# ArduinoUnoShield.net
KiCad netlist of a schematic drawn in Altium Designer
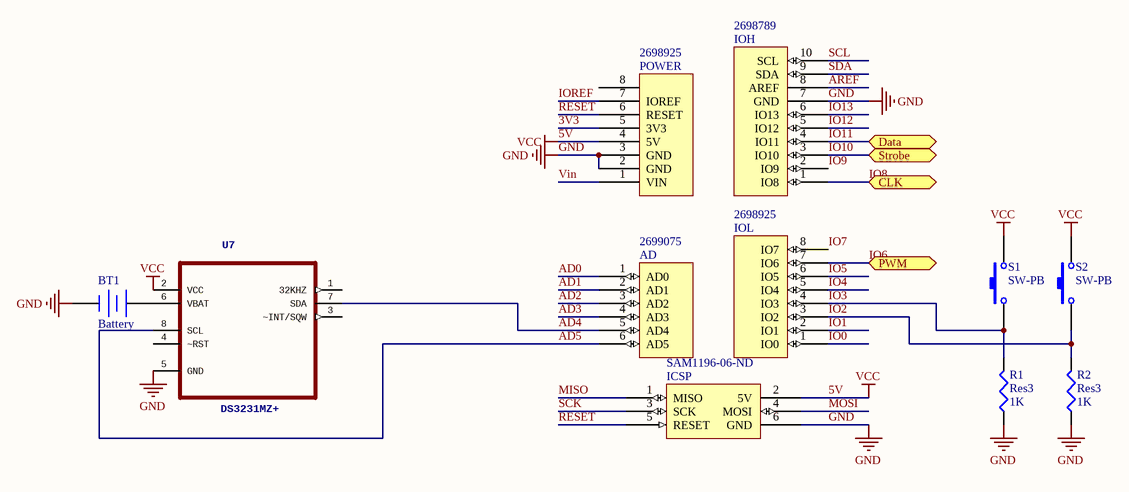
[diagram p0: ArduinoUnoShield.SchDoc]

(export (version "E")
  (design (tool "Eeschema 10.0.6"))
  (components
    (comp (ref "AD")
      (value "AD")
      (footprint "Header:Header 6x1 8.5mm")
      (fields (field (name "SUPPLIER PART NUMBER 4") "2699075"))
      (libsource (lib "Header") (part "AD"))
    )
    (comp (ref "BT1")
      (value "Battery")
      (footprint "BAT-2")
      (description "Multicell Battery")
      (fields (field (name "PUBLISHER") "Altium Limited"))
      (libsource (lib "Miscellaneous Devices") (part "Battery"))
    )
    (comp (ref "ICSP")
      (value "ICSP")
      (footprint "ICSP")
      (fields (field (name "SUPPLIER PART NUMBER 5") "SAM1196-06-ND"))
      (libsource (lib "Header") (part "ICSP"))
    )
    (comp (ref "IOH")
      (value "IOH")
      (footprint "Header:Header 10x1 8.5mm")
      (fields (field (name "SUPPLIER PART NUMBER 3") "2698789"))
      (libsource (lib "Header") (part "IOH"))
    )
    (comp (ref "IOL")
      (value "IOL")
      (footprint "Header 8x1 8.5mm")
      (fields (field (name "SUPPLIER PART NUMBER 4") "2698925"))
      (libsource (lib "Header") (part "IOL"))
    )
    (comp (ref "POWER")
      (value "POWER_UNO")
      (footprint "Header 8x1 8.5mm")
      (fields (field (name "SUPPLIER PART NUMBER 4") "2698925"))
      (libsource (lib "Header") (part "POWER_UNO"))
    )
    (comp (ref "R1")
      (value "Res3")
      (footprint "J1-0603")
      (description "Resistor")
      (fields (field (name "ALTIUM_VALUE") "1K") (field (name "PUBLISHER") "Altium Limited"))
      (libsource (lib "Miscellaneous Devices") (part "Res3"))
    )
    (comp (ref "R2")
      (value "Res3")
      (footprint "J1-0603")
      (description "Resistor")
      (fields (field (name "ALTIUM_VALUE") "1K") (field (name "PUBLISHER") "Altium Limited"))
      (libsource (lib "Miscellaneous Devices") (part "Res3"))
    )
    (comp (ref "S1")
      (value "SW-PB")
      (footprint "SPST-2")
      (description "Switch")
      (fields (field (name "PUBLISHER") "Altium Limited"))
      (libsource (lib "Miscellaneous Devices") (part "SW-PB"))
    )
    (comp (ref "S2")
      (value "SW-PB")
      (footprint "SPST-2")
      (description "Switch")
      (fields (field (name "PUBLISHER") "Altium Limited"))
      (libsource (lib "Miscellaneous Devices") (part "SW-PB"))
    )
    (comp (ref "U7")
      (value "DS3231MZ+")
      (footprint "SOIC8_150MIL")
      (fields (field (name "MF") "Maxim Integrated"))
      (libsource (lib "DS3231MZ_") (part "DS3231MZ+"))
    )
  )
  (nets
    (net (code "1") (name "/3V3") (class "Default")
      (node (ref "POWER") (pin "5") (pinfunction "3V3_5") (pintype "power_in"))
    )
    (net (code "3") (name "/AD0") (class "Default")
      (node (ref "AD") (pin "1") (pinfunction "AD0_1") (pintype "bidirectional"))
    )
    (net (code "4") (name "/AD1") (class "Default")
      (node (ref "AD") (pin "2") (pinfunction "AD1_2") (pintype "bidirectional"))
    )
    (net (code "5") (name "/AD2") (class "Default")
      (node (ref "AD") (pin "3") (pinfunction "AD2_3") (pintype "bidirectional"))
    )
    (net (code "6") (name "/AD3") (class "Default")
      (node (ref "AD") (pin "4") (pinfunction "AD3_4") (pintype "bidirectional"))
    )
    (net (code "7") (name "/AD4") (class "Default")
      (node (ref "AD") (pin "5") (pinfunction "AD4_5") (pintype "bidirectional"))
      (node (ref "U7") (pin "7") (pinfunction "SDA_7") (pintype "passive"))
    )
    (net (code "8") (name "/AD5") (class "Default")
      (node (ref "AD") (pin "6") (pinfunction "AD5_6") (pintype "bidirectional"))
      (node (ref "U7") (pin "8") (pinfunction "SCL_8") (pintype "passive"))
    )
    (net (code "9") (name "/AREF") (class "Default")
      (node (ref "IOH") (pin "8") (pinfunction "AREF_8") (pintype "passive"))
    )
    (net (code "10") (name "/IO0") (class "Default")
      (node (ref "IOL") (pin "1") (pinfunction "IO0_1") (pintype "bidirectional"))
    )
    (net (code "11") (name "/IO1") (class "Default")
      (node (ref "IOL") (pin "2") (pinfunction "IO1_2") (pintype "bidirectional"))
    )
    (net (code "12") (name "/IO2") (class "Default")
      (node (ref "IOL") (pin "3") (pinfunction "IO2_3") (pintype "bidirectional"))
      (node (ref "R2") (pin "2") (pinfunction "2_2") (pintype "passive"))
      (node (ref "S2") (pin "1") (pinfunction "1_1") (pintype "passive"))
    )
    (net (code "13") (name "/IO3") (class "Default")
      (node (ref "IOL") (pin "4") (pinfunction "IO3_4") (pintype "bidirectional"))
      (node (ref "R1") (pin "2") (pinfunction "2_2") (pintype "passive"))
      (node (ref "S1") (pin "1") (pinfunction "1_1") (pintype "passive"))
    )
    (net (code "14") (name "/IO4") (class "Default")
      (node (ref "IOL") (pin "5") (pinfunction "IO4_5") (pintype "bidirectional"))
    )
    (net (code "15") (name "/IO5") (class "Default")
      (node (ref "IOL") (pin "6") (pinfunction "IO5_6") (pintype "bidirectional"))
    )
    (net (code "16") (name "/IO6") (class "Default")
      (node (ref "IOL") (pin "7") (pinfunction "IO6_7") (pintype "bidirectional"))
    )
    (net (code "17") (name "/IO7") (class "Default")
      (node (ref "IOL") (pin "8") (pinfunction "IO7_8") (pintype "bidirectional"))
    )
    (net (code "18") (name "/IO8") (class "Default")
      (node (ref "IOH") (pin "1") (pinfunction "IO8_1") (pintype "bidirectional"))
    )
    (net (code "19") (name "/IO9") (class "Default")
      (node (ref "IOH") (pin "2") (pinfunction "IO9_2") (pintype "bidirectional"))
    )
    (net (code "20") (name "/IO10") (class "Default")
      (node (ref "IOH") (pin "3") (pinfunction "IO10_3") (pintype "bidirectional"))
    )
    (net (code "21") (name "/IO11") (class "Default")
      (node (ref "IOH") (pin "4") (pinfunction "IO11_4") (pintype "bidirectional"))
    )
    (net (code "22") (name "/IO12") (class "Default")
      (node (ref "IOH") (pin "5") (pinfunction "IO12_5") (pintype "bidirectional"))
    )
    (net (code "23") (name "/IO13") (class "Default")
      (node (ref "IOH") (pin "6") (pinfunction "IO13_6") (pintype "bidirectional"))
    )
    (net (code "24") (name "/IOREF") (class "Default")
      (node (ref "POWER") (pin "7") (pinfunction "IOREF_7") (pintype "power_in"))
    )
    (net (code "25") (name "/MISO") (class "Default")
      (node (ref "ICSP") (pin "1") (pinfunction "MISO_1") (pintype "bidirectional"))
    )
    (net (code "26") (name "/MOSI") (class "Default")
      (node (ref "ICSP") (pin "4") (pinfunction "MOSI_4") (pintype "bidirectional"))
    )
    (net (code "27") (name "/RESET") (class "Default")
      (node (ref "ICSP") (pin "5") (pinfunction "RESET_5") (pintype "input"))
      (node (ref "POWER") (pin "6") (pinfunction "RESET_6") (pintype "passive"))
    )
    (net (code "28") (name "/SCK") (class "Default")
      (node (ref "ICSP") (pin "3") (pinfunction "SCK_3") (pintype "bidirectional"))
    )
    (net (code "29") (name "/SCL") (class "Default")
      (node (ref "IOH") (pin "10") (pinfunction "SCL_10") (pintype "bidirectional"))
    )
    (net (code "30") (name "/SDA") (class "Default")
      (node (ref "IOH") (pin "9") (pinfunction "SDA_9") (pintype "bidirectional"))
    )
    (net (code "31") (name "/Vin") (class "Default")
      (node (ref "POWER") (pin "1") (pinfunction "VIN_1") (pintype "power_in"))
    )
    (net (code "32") (name "GND") (class "Default")
      (node (ref "BT1") (pin "2") (pinfunction "-_2") (pintype "passive"))
      (node (ref "ICSP") (pin "6") (pinfunction "GND_6") (pintype "power_in"))
      (node (ref "IOH") (pin "7") (pinfunction "GND_7") (pintype "power_in"))
      (node (ref "POWER") (pin "2") (pinfunction "GND_2") (pintype "power_in"))
      (node (ref "POWER") (pin "3") (pinfunction "GND_3") (pintype "power_in"))
      (node (ref "R1") (pin "1") (pinfunction "1_1") (pintype "passive"))
      (node (ref "R2") (pin "1") (pinfunction "1_1") (pintype "passive"))
      (node (ref "U7") (pin "5") (pinfunction "GND_5") (pintype "passive"))
    )
    (net (code "33") (name "Net-(BT1-+)") (class "Default")
      (node (ref "BT1") (pin "1") (pinfunction "+_1") (pintype "passive"))
      (node (ref "U7") (pin "6") (pinfunction "VBAT_6") (pintype "power_in"))
    )
    (net (code "34") (name "VCC") (class "Default")
      (node (ref "ICSP") (pin "2") (pinfunction "5V_2") (pintype "power_in"))
      (node (ref "POWER") (pin "4") (pinfunction "5V_4") (pintype "power_in"))
      (node (ref "S1") (pin "2") (pinfunction "2_2") (pintype "passive"))
      (node (ref "S2") (pin "2") (pinfunction "2_2") (pintype "passive"))
      (node (ref "U7") (pin "2") (pinfunction "VCC_2") (pintype "power_in"))
    )
    (net (code "35") (name "unconnected-(POWER-Pad8)") (class "Default")
      (node (ref "POWER") (pin "8") (pintype "passive"))
    )
    (net (code "36") (name "unconnected-(U7-32KHZ-Pad1)") (class "Default")
      (node (ref "U7") (pin "1") (pinfunction "32KHZ_1") (pintype "output"))
    )
    (net (code "37") (name "unconnected-(U7-~INT{slash}SQW-Pad3)") (class "Default")
      (node (ref "U7") (pin "3") (pinfunction "~INT/SQW_3") (pintype "output"))
    )
    (net (code "38") (name "unconnected-(U7-~RST-Pad4)") (class "Default")
      (node (ref "U7") (pin "4") (pinfunction "~RST_4") (pintype "passive"))
    )
  )
)
